# Overview.net
KiCad netlist of a schematic drawn in Altium Designer
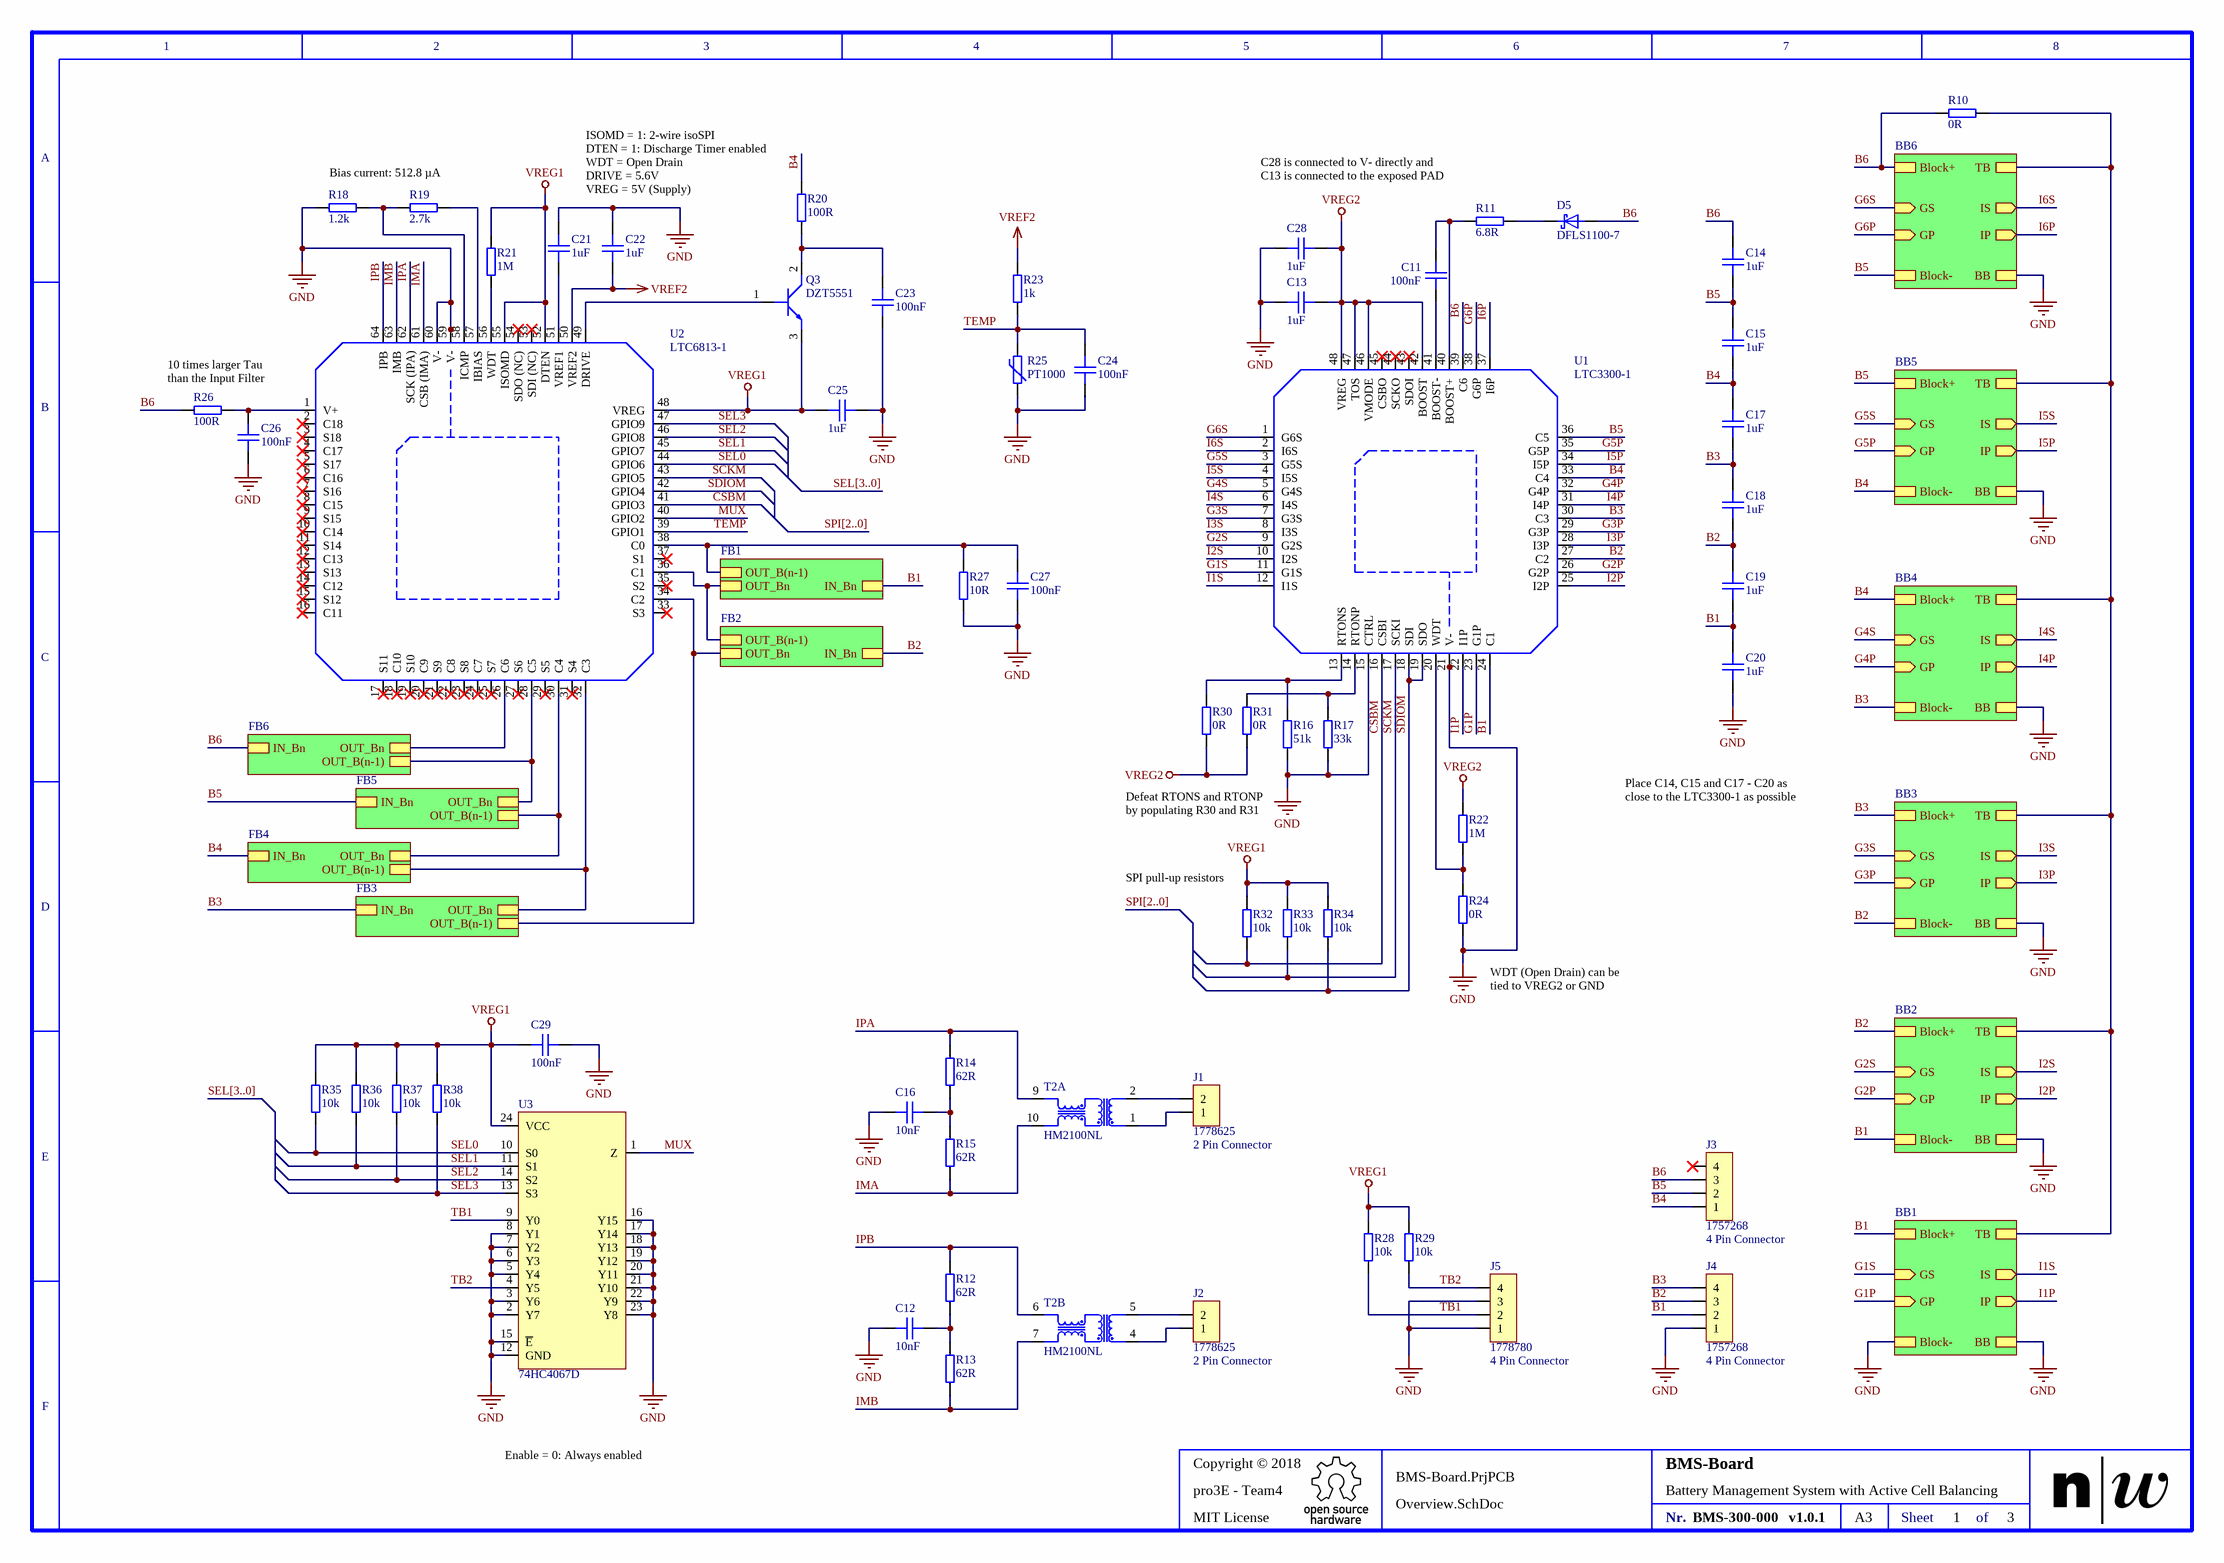
[diagram p0: Overview.SchDoc]

(export (version "E")
  (design (tool "Eeschema 10.0.6"))
  (components
    (comp (ref "C11")
      (value "100nF")
      (footprint "CAP 0603")
      (libsource (lib "SVNDatabase") (part "Capacitor"))
    )
    (comp (ref "C12")
      (value "10nF")
      (footprint "CAP 0603")
      (libsource (lib "SVNDatabase") (part "Capacitor"))
    )
    (comp (ref "C13")
      (value "1uF")
      (footprint "CAP 0603")
      (fields (field (name "TOLERANCE") "20%") (field (name "VOLTAGE") "16V"))
      (libsource (lib "SVNDatabase") (part "Capacitor"))
    )
    (comp (ref "C14")
      (value "1uF")
      (footprint "CAP 0603")
      (fields (field (name "TOLERANCE") "20%") (field (name "VOLTAGE") "16V"))
      (libsource (lib "SVNDatabase") (part "Capacitor"))
    )
    (comp (ref "C15")
      (value "1uF")
      (footprint "CAP 0603")
      (fields (field (name "TOLERANCE") "20%") (field (name "VOLTAGE") "16V"))
      (libsource (lib "SVNDatabase") (part "Capacitor"))
    )
    (comp (ref "C16")
      (value "10nF")
      (footprint "CAP 0603")
      (libsource (lib "SVNDatabase") (part "Capacitor"))
    )
    (comp (ref "C17")
      (value "1uF")
      (footprint "CAP 0603")
      (fields (field (name "TOLERANCE") "20%") (field (name "VOLTAGE") "16V"))
      (libsource (lib "SVNDatabase") (part "Capacitor"))
    )
    (comp (ref "C18")
      (value "1uF")
      (footprint "CAP 0603")
      (fields (field (name "TOLERANCE") "20%") (field (name "VOLTAGE") "16V"))
      (libsource (lib "SVNDatabase") (part "Capacitor"))
    )
    (comp (ref "C19")
      (value "1uF")
      (footprint "CAP 0603")
      (fields (field (name "TOLERANCE") "20%") (field (name "VOLTAGE") "16V"))
      (libsource (lib "SVNDatabase") (part "Capacitor"))
    )
    (comp (ref "C20")
      (value "1uF")
      (footprint "CAP 0603")
      (fields (field (name "TOLERANCE") "20%") (field (name "VOLTAGE") "16V"))
      (libsource (lib "SVNDatabase") (part "Capacitor"))
    )
    (comp (ref "C21")
      (value "1uF")
      (footprint "CAP 0603")
      (fields (field (name "TOLERANCE") "20%") (field (name "VOLTAGE") "16V"))
      (libsource (lib "SVNDatabase") (part "Capacitor"))
    )
    (comp (ref "C22")
      (value "1uF")
      (footprint "CAP 0603")
      (fields (field (name "TOLERANCE") "20%") (field (name "VOLTAGE") "16V"))
      (libsource (lib "SVNDatabase") (part "Capacitor"))
    )
    (comp (ref "C23")
      (value "100nF")
      (footprint "CAP 0603")
      (libsource (lib "SVNDatabase") (part "Capacitor"))
    )
    (comp (ref "C24")
      (value "100nF")
      (footprint "CAP 0603")
      (libsource (lib "SVNDatabase") (part "Capacitor"))
    )
    (comp (ref "C25")
      (value "1uF")
      (footprint "CAP 0603")
      (fields (field (name "TOLERANCE") "20%") (field (name "VOLTAGE") "16V"))
      (libsource (lib "SVNDatabase") (part "Capacitor"))
    )
    (comp (ref "C26")
      (value "100nF")
      (footprint "CAP 0603")
      (libsource (lib "SVNDatabase") (part "Capacitor"))
    )
    (comp (ref "C27")
      (value "100nF")
      (footprint "CAP 0603")
      (libsource (lib "SVNDatabase") (part "Capacitor"))
    )
    (comp (ref "C28")
      (value "1uF")
      (footprint "CAP 0603")
      (fields (field (name "TOLERANCE") "20%") (field (name "VOLTAGE") "16V"))
      (libsource (lib "SVNDatabase") (part "Capacitor"))
    )
    (comp (ref "C29")
      (value "100nF")
      (footprint "CAP 0603")
      (libsource (lib "SVNDatabase") (part "Capacitor"))
    )
    (comp (ref "D5")
      (value "DFLS1100-7")
      (footprint "PowerDI-123")
      (libsource (lib "SVNDatabase") (part "Schottky Diode"))
    )
    (comp (ref "J1")
      (value "1778625")
      (footprint "PTSM 0.5 2 HH THT")
      (description "2 Pin Connector")
      (fields (field (name "DESC") "2 Pin Connector"))
      (libsource (lib "SVNDatabase") (part "2 Pin"))
    )
    (comp (ref "J2")
      (value "1778625")
      (footprint "PTSM 0.5 2 HH THT")
      (description "2 Pin Connector")
      (fields (field (name "DESC") "2 Pin Connector"))
      (libsource (lib "SVNDatabase") (part "2 Pin"))
    )
    (comp (ref "J3")
      (value "1757268")
      (footprint "MSTBA 2.5 4 G THT 5.08")
      (description "4 Pin Connector")
      (fields (field (name "DESCR") "4 Pin Connector"))
      (libsource (lib "SVNDatabase") (part "4 Pin"))
    )
    (comp (ref "J4")
      (value "1757268")
      (footprint "MSTBA 2.5 4 G THT 5.08")
      (description "4 Pin Connector")
      (fields (field (name "DESCR") "4 Pin Connector"))
      (libsource (lib "SVNDatabase") (part "4 Pin"))
    )
    (comp (ref "J5")
      (value "1778780")
      (footprint "PTSM 0.5 4 HH THT")
      (description "4 Pin Connector")
      (fields (field (name "DESCR") "4 Pin Connector"))
      (libsource (lib "SVNDatabase") (part "4 Pin"))
    )
    (comp (ref "Q3") (value "DZT5551") (footprint "SOT-223") (libsource (lib "SVNDatabase") (part "BJT NPN")))
    (comp (ref "R10")
      (value "0R")
      (footprint "1206")
      (fields (field (name "TOLERANCE") "1%"))
      (libsource (lib "SVNDatabase") (part "R"))
    )
    (comp (ref "R11")
      (value "6.8R")
      (footprint "0603")
      (fields (field (name "TOLERANCE") "1%"))
      (libsource (lib "SVNDatabase") (part "R"))
    )
    (comp (ref "R12")
      (value "62R")
      (footprint "0603")
      (fields (field (name "TOLERANCE") "1%"))
      (libsource (lib "SVNDatabase") (part "R"))
    )
    (comp (ref "R13")
      (value "62R")
      (footprint "0603")
      (fields (field (name "TOLERANCE") "1%"))
      (libsource (lib "SVNDatabase") (part "R"))
    )
    (comp (ref "R14")
      (value "62R")
      (footprint "0603")
      (fields (field (name "TOLERANCE") "1%"))
      (libsource (lib "SVNDatabase") (part "R"))
    )
    (comp (ref "R15")
      (value "62R")
      (footprint "0603")
      (fields (field (name "TOLERANCE") "1%"))
      (libsource (lib "SVNDatabase") (part "R"))
    )
    (comp (ref "R16")
      (value "51k")
      (footprint "0603")
      (fields (field (name "TOLERANCE") "1%"))
      (libsource (lib "SVNDatabase") (part "R"))
    )
    (comp (ref "R17")
      (value "33k")
      (footprint "0603")
      (fields (field (name "TOLERANCE") "1%"))
      (libsource (lib "SVNDatabase") (part "R"))
    )
    (comp (ref "R18")
      (value "1.2k")
      (footprint "0603")
      (fields (field (name "TOLERANCE") "1%"))
      (libsource (lib "SVNDatabase") (part "R"))
    )
    (comp (ref "R19")
      (value "2.7k")
      (footprint "0603")
      (fields (field (name "TOLERANCE") "1%"))
      (libsource (lib "SVNDatabase") (part "R"))
    )
    (comp (ref "R20")
      (value "100R")
      (footprint "0603")
      (fields (field (name "TOLERANCE") "1%"))
      (libsource (lib "SVNDatabase") (part "R"))
    )
    (comp (ref "R21")
      (value "1M")
      (footprint "0603")
      (fields (field (name "TOLERANCE") "1%"))
      (libsource (lib "SVNDatabase") (part "R"))
    )
    (comp (ref "R22")
      (value "1M")
      (footprint "0603")
      (fields (field (name "TOLERANCE") "1%"))
      (libsource (lib "SVNDatabase") (part "R"))
    )
    (comp (ref "R23")
      (value "1k")
      (footprint "0603")
      (fields (field (name "TOLERANCE") "1%"))
      (libsource (lib "SVNDatabase") (part "R"))
    )
    (comp (ref "R24")
      (value "0R")
      (footprint "0603")
      (fields (field (name "TOLERANCE") "1%"))
      (libsource (lib "SVNDatabase") (part "R"))
    )
    (comp (ref "R25")
      (value "PT1000")
      (footprint "1206")
      (libsource (lib "SVNDatabase") (part "R Thermistor"))
    )
    (comp (ref "R26")
      (value "100R")
      (footprint "0603")
      (fields (field (name "TOLERANCE") "1%"))
      (libsource (lib "SVNDatabase") (part "R"))
    )
    (comp (ref "R27")
      (value "10R")
      (footprint "0603")
      (fields (field (name "TOLERANCE") "1%"))
      (libsource (lib "SVNDatabase") (part "R"))
    )
    (comp (ref "R28")
      (value "10k")
      (footprint "0603")
      (fields (field (name "TOLERANCE") "1%"))
      (libsource (lib "SVNDatabase") (part "R"))
    )
    (comp (ref "R29")
      (value "10k")
      (footprint "0603")
      (fields (field (name "TOLERANCE") "1%"))
      (libsource (lib "SVNDatabase") (part "R"))
    )
    (comp (ref "R30")
      (value "0R")
      (footprint "0603")
      (fields (field (name "TOLERANCE") "1%"))
      (libsource (lib "SVNDatabase") (part "R"))
    )
    (comp (ref "R31")
      (value "0R")
      (footprint "0603")
      (fields (field (name "TOLERANCE") "1%"))
      (libsource (lib "SVNDatabase") (part "R"))
    )
    (comp (ref "R32")
      (value "10k")
      (footprint "0603")
      (fields (field (name "TOLERANCE") "1%"))
      (libsource (lib "SVNDatabase") (part "R"))
    )
    (comp (ref "R33")
      (value "10k")
      (footprint "0603")
      (fields (field (name "TOLERANCE") "1%"))
      (libsource (lib "SVNDatabase") (part "R"))
    )
    (comp (ref "R34")
      (value "10k")
      (footprint "0603")
      (fields (field (name "TOLERANCE") "1%"))
      (libsource (lib "SVNDatabase") (part "R"))
    )
    (comp (ref "R35")
      (value "10k")
      (footprint "0603")
      (fields (field (name "TOLERANCE") "1%"))
      (libsource (lib "SVNDatabase") (part "R"))
    )
    (comp (ref "R36")
      (value "10k")
      (footprint "0603")
      (fields (field (name "TOLERANCE") "1%"))
      (libsource (lib "SVNDatabase") (part "R"))
    )
    (comp (ref "R37")
      (value "10k")
      (footprint "0603")
      (fields (field (name "TOLERANCE") "1%"))
      (libsource (lib "SVNDatabase") (part "R"))
    )
    (comp (ref "R38")
      (value "10k")
      (footprint "0603")
      (fields (field (name "TOLERANCE") "1%"))
      (libsource (lib "SVNDatabase") (part "R"))
    )
    (comp (ref "T2")
      (value "HM2100NL")
      (footprint "HM2100NL")
      (description "BMS Communication Transformer with Choke")
      (fields (field (name "TOLERANCE") "50%"))
      (libsource (lib "SVNDatabase") (part "HM2100NL"))
    )
    (comp (ref "U1")
      (value "LTC3300-1")
      (footprint "eLQFP-48")
      (description "Battery Balancer")
      (libsource (lib "SVNDatabase") (part "LTC3300"))
    )
    (comp (ref "U2")
      (value "LTC6813-1")
      (footprint "eLQFP-64")
      (description "Battery Monitor")
      (libsource (lib "SVNDatabase") (part "LTC6813"))
    )
    (comp (ref "U3")
      (value "74HC4067D")
      (footprint "SO-24")
      (description "MUX 16:1")
      (libsource (lib "SVNDatabase") (part "74HC4067D"))
    )
  )
  (nets
    (net (code "4") (name "/B1") (class "Default")
      (node (ref "C19") (pin "1") (pinfunction "1_1") (pintype "passive"))
      (node (ref "C20") (pin "2") (pinfunction "2_2") (pintype "passive"))
      (node (ref "J4") (pin "2") (pinfunction "2_2") (pintype "passive"))
      (node (ref "U1") (pin "24") (pinfunction "C1_24") (pintype "passive"))
    )
    (net (code "5") (name "/B2") (class "Default")
      (node (ref "C18") (pin "1") (pinfunction "1_1") (pintype "passive"))
      (node (ref "C19") (pin "2") (pinfunction "2_2") (pintype "passive"))
      (node (ref "J4") (pin "3") (pinfunction "3_3") (pintype "passive"))
      (node (ref "U1") (pin "27") (pinfunction "C2_27") (pintype "passive"))
    )
    (net (code "6") (name "/B3") (class "Default")
      (node (ref "C17") (pin "1") (pinfunction "1_1") (pintype "passive"))
      (node (ref "C18") (pin "2") (pinfunction "2_2") (pintype "passive"))
      (node (ref "J4") (pin "4") (pinfunction "4_4") (pintype "passive"))
      (node (ref "U1") (pin "30") (pinfunction "C3_30") (pintype "passive"))
    )
    (net (code "7") (name "/B4") (class "Default")
      (node (ref "C15") (pin "1") (pinfunction "1_1") (pintype "passive"))
      (node (ref "C17") (pin "2") (pinfunction "2_2") (pintype "passive"))
      (node (ref "J3") (pin "1") (pinfunction "1_1") (pintype "passive"))
      (node (ref "R20") (pin "2") (pinfunction "2_2") (pintype "passive"))
      (node (ref "U1") (pin "33") (pinfunction "C4_33") (pintype "passive"))
    )
    (net (code "8") (name "/B5") (class "Default")
      (node (ref "C14") (pin "1") (pinfunction "1_1") (pintype "passive"))
      (node (ref "C15") (pin "2") (pinfunction "2_2") (pintype "passive"))
      (node (ref "J3") (pin "2") (pinfunction "2_2") (pintype "passive"))
      (node (ref "U1") (pin "36") (pinfunction "C5_36") (pintype "passive"))
    )
    (net (code "9") (name "/B6") (class "Default")
      (node (ref "C14") (pin "2") (pinfunction "2_2") (pintype "passive"))
      (node (ref "D5") (pin "1") (pinfunction "1_1") (pintype "passive"))
      (node (ref "J3") (pin "3") (pinfunction "3_3") (pintype "passive"))
      (node (ref "R10") (pin "1") (pinfunction "1_1") (pintype "passive"))
      (node (ref "R26") (pin "1") (pinfunction "1_1") (pintype "passive"))
      (node (ref "U1") (pin "39") (pinfunction "C6_39") (pintype "passive"))
    )
    (net (code "10") (name "/CSBM") (class "Default")
      (node (ref "R32") (pin "1") (pinfunction "1_1") (pintype "passive"))
      (node (ref "U1") (pin "16") (pinfunction "CSBI_16") (pintype "passive"))
      (node (ref "U2") (pin "41") (pinfunction "GPIO3_41") (pintype "passive"))
    )
    (net (code "11") (name "/G1P") (class "Default")
      (node (ref "U1") (pin "23") (pinfunction "G1P_23") (pintype "passive"))
    )
    (net (code "12") (name "/G1S") (class "Default")
      (node (ref "U1") (pin "11") (pinfunction "G1S_11") (pintype "passive"))
    )
    (net (code "13") (name "/G2P") (class "Default")
      (node (ref "U1") (pin "26") (pinfunction "G2P_26") (pintype "passive"))
    )
    (net (code "14") (name "/G2S") (class "Default")
      (node (ref "U1") (pin "9") (pinfunction "G2S_9") (pintype "passive"))
    )
    (net (code "15") (name "/G3P") (class "Default")
      (node (ref "U1") (pin "29") (pinfunction "G3P_29") (pintype "passive"))
    )
    (net (code "16") (name "/G3S") (class "Default")
      (node (ref "U1") (pin "7") (pinfunction "G3S_7") (pintype "passive"))
    )
    (net (code "17") (name "/G4P") (class "Default")
      (node (ref "U1") (pin "32") (pinfunction "G4P_32") (pintype "passive"))
    )
    (net (code "18") (name "/G4S") (class "Default")
      (node (ref "U1") (pin "5") (pinfunction "G4S_5") (pintype "passive"))
    )
    (net (code "19") (name "/G5P") (class "Default")
      (node (ref "U1") (pin "35") (pinfunction "G5P_35") (pintype "passive"))
    )
    (net (code "20") (name "/G5S") (class "Default")
      (node (ref "U1") (pin "3") (pinfunction "G5S_3") (pintype "passive"))
    )
    (net (code "21") (name "/G6P") (class "Default")
      (node (ref "U1") (pin "38") (pinfunction "G6P_38") (pintype "passive"))
    )
    (net (code "22") (name "/G6S") (class "Default")
      (node (ref "U1") (pin "1") (pinfunction "G6S_1") (pintype "passive"))
    )
    (net (code "23") (name "/I1P") (class "Default")
      (node (ref "U1") (pin "22") (pinfunction "I1P_22") (pintype "passive"))
    )
    (net (code "24") (name "/I1S") (class "Default")
      (node (ref "U1") (pin "12") (pinfunction "I1S_12") (pintype "passive"))
    )
    (net (code "25") (name "/I2P") (class "Default")
      (node (ref "U1") (pin "25") (pinfunction "I2P_25") (pintype "passive"))
    )
    (net (code "26") (name "/I2S") (class "Default")
      (node (ref "U1") (pin "10") (pinfunction "I2S_10") (pintype "passive"))
    )
    (net (code "27") (name "/I3P") (class "Default")
      (node (ref "U1") (pin "28") (pinfunction "I3P_28") (pintype "passive"))
    )
    (net (code "28") (name "/I3S") (class "Default")
      (node (ref "U1") (pin "8") (pinfunction "I3S_8") (pintype "passive"))
    )
    (net (code "29") (name "/I4P") (class "Default")
      (node (ref "U1") (pin "31") (pinfunction "I4P_31") (pintype "passive"))
    )
    (net (code "30") (name "/I4S") (class "Default")
      (node (ref "U1") (pin "6") (pinfunction "I4S_6") (pintype "passive"))
    )
    (net (code "31") (name "/I5P") (class "Default")
      (node (ref "U1") (pin "34") (pinfunction "I5P_34") (pintype "passive"))
    )
    (net (code "32") (name "/I5S") (class "Default")
      (node (ref "U1") (pin "4") (pinfunction "I5S_4") (pintype "passive"))
    )
    (net (code "33") (name "/I6P") (class "Default")
      (node (ref "U1") (pin "37") (pinfunction "I6P_37") (pintype "passive"))
    )
    (net (code "34") (name "/I6S") (class "Default")
      (node (ref "U1") (pin "2") (pinfunction "I6S_2") (pintype "passive"))
    )
    (net (code "35") (name "/IMA") (class "Default")
      (node (ref "R15") (pin "2") (pinfunction "2_2") (pintype "passive"))
      (node (ref "T2") (pin "10") (pinfunction "10_10") (pintype "passive"))
      (node (ref "U2") (pin "61") (pinfunction "CSB_(IMA)_61") (pintype "passive"))
    )
    (net (code "36") (name "/IMB") (class "Default")
      (node (ref "R13") (pin "2") (pinfunction "2_2") (pintype "passive"))
      (node (ref "T2") (pin "7") (pinfunction "7_7") (pintype "passive"))
      (node (ref "U2") (pin "63") (pinfunction "IMB_63") (pintype "passive"))
    )
    (net (code "37") (name "/IPA") (class "Default")
      (node (ref "R14") (pin "1") (pinfunction "1_1") (pintype "passive"))
      (node (ref "T2") (pin "9") (pinfunction "9_9") (pintype "passive"))
      (node (ref "U2") (pin "62") (pinfunction "SCK_(IPA)_62") (pintype "passive"))
    )
    (net (code "38") (name "/IPB") (class "Default")
      (node (ref "R12") (pin "1") (pinfunction "1_1") (pintype "passive"))
      (node (ref "T2") (pin "6") (pinfunction "6_6") (pintype "passive"))
      (node (ref "U2") (pin "64") (pinfunction "IPB_64") (pintype "passive"))
    )
    (net (code "39") (name "/MUX") (class "Default")
      (node (ref "U2") (pin "40") (pinfunction "GPIO2_40") (pintype "passive"))
      (node (ref "U3") (pin "1") (pinfunction "Z_1") (pintype "passive"))
    )
    (net (code "40") (name "/OUT_B(n-1)") (class "Default")
      (node (ref "U2") (pin "36") (pinfunction "C1_36") (pintype "passive"))
    )
    (net (code "41") (name "/OUT_B(n-1)_1") (class "Default")
      (node (ref "U2") (pin "30") (pinfunction "C4_30") (pintype "passive"))
    )
    (net (code "42") (name "/OUT_B(n-1)_2") (class "Default")
      (node (ref "U2") (pin "32") (pinfunction "C3_32") (pintype "passive"))
    )
    (net (code "43") (name "/OUT_B(n-1)_3") (class "Default")
      (node (ref "U2") (pin "28") (pinfunction "C5_28") (pintype "passive"))
    )
    (net (code "44") (name "/OUT_B(n-1)_4") (class "Default")
      (node (ref "U2") (pin "34") (pinfunction "C2_34") (pintype "passive"))
    )
    (net (code "45") (name "/OUT_B(n-1)_5") (class "Default")
      (node (ref "C27") (pin "2") (pinfunction "2_2") (pintype "passive"))
      (node (ref "R27") (pin "2") (pinfunction "2_2") (pintype "passive"))
      (node (ref "U2") (pin "38") (pinfunction "C0_38") (pintype "passive"))
    )
    (net (code "46") (name "/OUT_Bn") (class "Default")
      (node (ref "U2") (pin "26") (pinfunction "C6_26") (pintype "passive"))
    )
    (net (code "47") (name "/SCKM") (class "Default")
      (node (ref "R33") (pin "1") (pinfunction "1_1") (pintype "passive"))
      (node (ref "U1") (pin "17") (pinfunction "SCKI_17") (pintype "passive"))
      (node (ref "U2") (pin "43") (pinfunction "GPIO5_43") (pintype "passive"))
    )
    (net (code "48") (name "/SDIOM") (class "Default")
      (node (ref "R34") (pin "1") (pinfunction "1_1") (pintype "passive"))
      (node (ref "U1") (pin "18") (pinfunction "SDI_18") (pintype "passive"))
      (node (ref "U1") (pin "19") (pinfunction "SDO_19") (pintype "passive"))
      (node (ref "U2") (pin "42") (pinfunction "GPIO4_42") (pintype "passive"))
    )
    (net (code "49") (name "/SEL0") (class "Default")
      (node (ref "R35") (pin "1") (pinfunction "1_1") (pintype "passive"))
      (node (ref "U2") (pin "44") (pinfunction "GPIO6_44") (pintype "passive"))
      (node (ref "U3") (pin "10") (pinfunction "S0_10") (pintype "passive"))
    )
    (net (code "50") (name "/SEL1") (class "Default")
      (node (ref "R36") (pin "1") (pinfunction "1_1") (pintype "passive"))
      (node (ref "U2") (pin "45") (pinfunction "GPIO7_45") (pintype "passive"))
      (node (ref "U3") (pin "11") (pinfunction "S1_11") (pintype "passive"))
    )
    (net (code "51") (name "/SEL2") (class "Default")
      (node (ref "R37") (pin "1") (pinfunction "1_1") (pintype "passive"))
      (node (ref "U2") (pin "46") (pinfunction "GPIO8_46") (pintype "passive"))
      (node (ref "U3") (pin "14") (pinfunction "S2_14") (pintype "passive"))
    )
    (net (code "52") (name "/SEL3") (class "Default")
      (node (ref "R38") (pin "1") (pinfunction "1_1") (pintype "passive"))
      (node (ref "U2") (pin "47") (pinfunction "GPIO9_47") (pintype "passive"))
      (node (ref "U3") (pin "13") (pinfunction "S3_13") (pintype "passive"))
    )
    (net (code "55") (name "/TB") (class "Default")
      (node (ref "R10") (pin "2") (pinfunction "2_2") (pintype "passive"))
    )
    (net (code "56") (name "/TB1") (class "Default")
      (node (ref "J5") (pin "2") (pinfunction "2_2") (pintype "passive"))
      (node (ref "R28") (pin "1") (pinfunction "1_1") (pintype "passive"))
      (node (ref "U3") (pin "9") (pinfunction "Y0_9") (pintype "passive"))
    )
    (net (code "57") (name "/TB2") (class "Default")
      (node (ref "J5") (pin "4") (pinfunction "4_4") (pintype "passive"))
      (node (ref "R29") (pin "1") (pinfunction "1_1") (pintype "passive"))
      (node (ref "U3") (pin "4") (pinfunction "Y5_4") (pintype "passive"))
    )
    (net (code "58") (name "/TEMP") (class "Default")
      (node (ref "C24") (pin "2") (pinfunction "2_2") (pintype "passive"))
      (node (ref "R23") (pin "1") (pinfunction "1_1") (pintype "passive"))
      (node (ref "R25") (pin "1") (pinfunction "1_1") (pintype "passive"))
      (node (ref "U2") (pin "39") (pinfunction "GPIO1_39") (pintype "passive"))
    )
    (net (code "59") (name "GND") (class "Default")
      (node (ref "C12") (pin "1") (pinfunction "1_1") (pintype "passive"))
      (node (ref "C13") (pin "2") (pinfunction "2_2") (pintype "passive"))
      (node (ref "C16") (pin "1") (pinfunction "1_1") (pintype "passive"))
      (node (ref "C20") (pin "1") (pinfunction "1_1") (pintype "passive"))
      (node (ref "C21") (pin "2") (pinfunction "2_2") (pintype "passive"))
      (node (ref "C22") (pin "1") (pinfunction "1_1") (pintype "passive"))
      (node (ref "C23") (pin "1") (pinfunction "1_1") (pintype "passive"))
      (node (ref "C24") (pin "1") (pinfunction "1_1") (pintype "passive"))
      (node (ref "C25") (pin "1") (pinfunction "1_1") (pintype "passive"))
      (node (ref "C26") (pin "1") (pinfunction "1_1") (pintype "passive"))
      (node (ref "C27") (pin "1") (pinfunction "1_1") (pintype "passive"))
      (node (ref "C28") (pin "1") (pinfunction "1_1") (pintype "passive"))
      (node (ref "C29") (pin "1") (pinfunction "1_1") (pintype "passive"))
      (node (ref "J4") (pin "1") (pinfunction "1_1") (pintype "passive"))
      (node (ref "J5") (pin "1") (pinfunction "1_1") (pintype "passive"))
      (node (ref "J5") (pin "3") (pinfunction "3_3") (pintype "passive"))
      (node (ref "R16") (pin "1") (pinfunction "1_1") (pintype "passive"))
      (node (ref "R17") (pin "1") (pinfunction "1_1") (pintype "passive"))
      (node (ref "R18") (pin "2") (pinfunction "2_2") (pintype "passive"))
      (node (ref "R24") (pin "1") (pinfunction "1_1") (pintype "passive"))
      (node (ref "R25") (pin "2") (pinfunction "2_2") (pintype "passive"))
      (node (ref "R27") (pin "1") (pinfunction "1_1") (pintype "passive"))
      (node (ref "U1") (pin "15") (pinfunction "CTRL_15") (pintype "passive"))
      (node (ref "U1") (pin "21") (pinfunction "V-_21") (pintype "passive"))
      (node (ref "U1") (pin "49") (pinfunction "V-_49") (pintype "passive"))
      (node (ref "U2") (pin "59") (pinfunction "V-_59") (pintype "passive"))
      (node (ref "U2") (pin "60") (pinfunction "V-_60") (pintype "passive"))
      (node (ref "U2") (pin "65") (pinfunction "V-_65") (pintype "passive"))
      (node (ref "U3") (pin "12") (pinfunction "GND_12") (pintype "passive"))
      (node (ref "U3") (pin "15") (pinfunction "~{E}_15") (pintype "passive"))
      (node (ref "U3") (pin "16") (pinfunction "Y15_16") (pintype "passive"))
      (node (ref "U3") (pin "17") (pinfunction "Y14_17") (pintype "passive"))
      (node (ref "U3") (pin "18") (pinfunction "Y13_18") (pintype "passive"))
      (node (ref "U3") (pin "19") (pinfunction "Y12_19") (pintype "passive"))
      (node (ref "U3") (pin "2") (pinfunction "Y7_2") (pintype "passive"))
      (node (ref "U3") (pin "20") (pinfunction "Y11_20") (pintype "passive"))
      (node (ref "U3") (pin "21") (pinfunction "Y10_21") (pintype "passive"))
      (node (ref "U3") (pin "22") (pinfunction "Y9_22") (pintype "passive"))
      (node (ref "U3") (pin "23") (pinfunction "Y8_23") (pintype "passive"))
      (node (ref "U3") (pin "3") (pinfunction "Y6_3") (pintype "passive"))
      (node (ref "U3") (pin "5") (pinfunction "Y4_5") (pintype "passive"))
      (node (ref "U3") (pin "6") (pinfunction "Y3_6") (pintype "passive"))
      (node (ref "U3") (pin "7") (pinfunction "Y2_7") (pintype "passive"))
      (node (ref "U3") (pin "8") (pinfunction "Y1_8") (pintype "passive"))
    )
    (net (code "60") (name "Net-(C12-Pad2)") (class "Default")
      (node (ref "C12") (pin "2") (pinfunction "2_2") (pintype "passive"))
      (node (ref "R12") (pin "2") (pinfunction "2_2") (pintype "passive"))
      (node (ref "R13") (pin "1") (pinfunction "1_1") (pintype "passive"))
    )
    (net (code "61") (name "Net-(C16-Pad2)") (class "Default")
      (node (ref "C16") (pin "2") (pinfunction "2_2") (pintype "passive"))
      (node (ref "R14") (pin "2") (pinfunction "2_2") (pintype "passive"))
      (node (ref "R15") (pin "1") (pinfunction "1_1") (pintype "passive"))
    )
    (net (code "62") (name "Net-(D5-Pad2)") (class "Default")
      (node (ref "D5") (pin "2") (pinfunction "2_2") (pintype "passive"))
      (node (ref "R11") (pin "2") (pinfunction "2_2") (pintype "passive"))
    )
    (net (code "63") (name "Net-(J1-Pad1)") (class "Default")
      (node (ref "J1") (pin "1") (pinfunction "1_1") (pintype "passive"))
      (node (ref "T2") (pin "1") (pinfunction "1_1") (pintype "passive"))
    )
    (net (code "64") (name "Net-(J1-Pad2)") (class "Default")
      (node (ref "J1") (pin "2") (pinfunction "2_2") (pintype "passive"))
      (node (ref "T2") (pin "2") (pinfunction "2_2") (pintype "passive"))
    )
    (net (code "65") (name "Net-(J2-Pad1)") (class "Default")
      (node (ref "J2") (pin "1") (pinfunction "1_1") (pintype "passive"))
      (node (ref "T2") (pin "4") (pinfunction "4_4") (pintype "passive"))
    )
    (net (code "66") (name "Net-(J2-Pad2)") (class "Default")
      (node (ref "J2") (pin "2") (pinfunction "2_2") (pintype "passive"))
      (node (ref "T2") (pin "5") (pinfunction "5_5") (pintype "passive"))
    )
    (net (code "67") (name "Net-(Q3-D)") (class "Default")
      (node (ref "C23") (pin "2") (pinfunction "2_2") (pintype "passive"))
      (node (ref "Q3") (pin "2") (pinfunction "D_2") (pintype "passive"))
      (node (ref "R20") (pin "1") (pinfunction "1_1") (pintype "passive"))
    )
    (net (code "68") (name "Net-(Q3-G)") (class "Default")
      (node (ref "Q3") (pin "1") (pinfunction "G_1") (pintype "passive"))
      (node (ref "U2") (pin "49") (pinfunction "DRIVE_49") (pintype "passive"))
    )
    (net (code "69") (name "Net-(U1-BOOST+)") (class "Default")
      (node (ref "C11") (pin "2") (pinfunction "2_2") (pintype "passive"))
      (node (ref "R11") (pin "1") (pinfunction "1_1") (pintype "passive"))
      (node (ref "U1") (pin "40") (pinfunction "BOOST+_40") (pintype "passive"))
    )
    (net (code "70") (name "Net-(U1-BOOST-)") (class "Default")
      (node (ref "C11") (pin "1") (pinfunction "1_1") (pintype "passive"))
      (node (ref "U1") (pin "41") (pinfunction "BOOST-_41") (pintype "passive"))
    )
    (net (code "71") (name "Net-(U1-RTONP)") (class "Default")
      (node (ref "R17") (pin "2") (pinfunction "2_2") (pintype "passive"))
      (node (ref "R31") (pin "2") (pinfunction "2_2") (pintype "passive"))
      (node (ref "U1") (pin "14") (pinfunction "RTONP_14") (pintype "passive"))
    )
    (net (code "72") (name "Net-(U1-RTONS)") (class "Default")
      (node (ref "R16") (pin "2") (pinfunction "2_2") (pintype "passive"))
      (node (ref "R30") (pin "2") (pinfunction "2_2") (pintype "passive"))
      (node (ref "U1") (pin "13") (pinfunction "RTONS_13") (pintype "passive"))
    )
    (net (code "73") (name "Net-(U1-WDT)") (class "Default")
      (node (ref "R22") (pin "1") (pinfunction "1_1") (pintype "passive"))
      (node (ref "R24") (pin "2") (pinfunction "2_2") (pintype "passive"))
      (node (ref "U1") (pin "20") (pinfunction "WDT_20") (pintype "passive"))
    )
    (net (code "74") (name "Net-(U2-IBIAS)") (class "Default")
      (node (ref "R19") (pin "1") (pinfunction "1_1") (pintype "passive"))
      (node (ref "U2") (pin "57") (pinfunction "IBIAS_57") (pintype "passive"))
    )
    (net (code "75") (name "Net-(U2-ICMP)") (class "Default")
      (node (ref "R18") (pin "1") (pinfunction "1_1") (pintype "passive"))
      (node (ref "R19") (pin "2") (pinfunction "2_2") (pintype "passive"))
      (node (ref "U2") (pin "58") (pinfunction "ICMP_58") (pintype "passive"))
    )
    (net (code "76") (name "Net-(U2-V+)") (class "Default")
      (node (ref "C26") (pin "2") (pinfunction "2_2") (pintype "passive"))
      (node (ref "R26") (pin "2") (pinfunction "2_2") (pintype "passive"))
      (node (ref "U2") (pin "1") (pinfunction "V+_1") (pintype "passive"))
    )
    (net (code "77") (name "Net-(U2-VREF1)") (class "Default")
      (node (ref "C21") (pin "1") (pinfunction "1_1") (pintype "passive"))
      (node (ref "U2") (pin "51") (pinfunction "VREF1_51") (pintype "passive"))
    )
    (net (code "78") (name "Net-(U2-WDT)") (class "Default")
      (node (ref "R21") (pin "1") (pinfunction "1_1") (pintype "passive"))
      (node (ref "U2") (pin "56") (pinfunction "WDT_56") (pintype "passive"))
    )
    (net (code "79") (name "VREF2") (class "Default")
      (node (ref "C22") (pin "2") (pinfunction "2_2") (pintype "passive"))
      (node (ref "R23") (pin "2") (pinfunction "2_2") (pintype "passive"))
      (node (ref "U2") (pin "50") (pinfunction "VREF2_50") (pintype "passive"))
    )
    (net (code "80") (name "VREG1") (class "Default")
      (node (ref "C25") (pin "2") (pinfunction "2_2") (pintype "passive"))
      (node (ref "C29") (pin "2") (pinfunction "2_2") (pintype "passive"))
      (node (ref "Q3") (pin "3") (pinfunction "S_3") (pintype "passive"))
      (node (ref "R21") (pin "2") (pinfunction "2_2") (pintype "passive"))
      (node (ref "R28") (pin "2") (pinfunction "2_2") (pintype "passive"))
      (node (ref "R29") (pin "2") (pinfunction "2_2") (pintype "passive"))
      (node (ref "R32") (pin "2") (pinfunction "2_2") (pintype "passive"))
      (node (ref "R33") (pin "2") (pinfunction "2_2") (pintype "passive"))
      (node (ref "R34") (pin "2") (pinfunction "2_2") (pintype "passive"))
      (node (ref "R35") (pin "2") (pinfunction "2_2") (pintype "passive"))
      (node (ref "R36") (pin "2") (pinfunction "2_2") (pintype "passive"))
      (node (ref "R37") (pin "2") (pinfunction "2_2") (pintype "passive"))
      (node (ref "R38") (pin "2") (pinfunction "2_2") (pintype "passive"))
      (node (ref "U2") (pin "48") (pinfunction "VREG_48") (pintype "passive"))
      (node (ref "U2") (pin "52") (pinfunction "DTEN_52") (pintype "passive"))
      (node (ref "U2") (pin "55") (pinfunction "ISOMD_55") (pintype "passive"))
      (node (ref "U3") (pin "24") (pinfunction "VCC_24") (pintype "passive"))
    )
    (net (code "81") (name "VREG2") (class "Default")
      (node (ref "C13") (pin "1") (pinfunction "1_1") (pintype "passive"))
      (node (ref "C28") (pin "2") (pinfunction "2_2") (pintype "passive"))
      (node (ref "R22") (pin "2") (pinfunction "2_2") (pintype "passive"))
      (node (ref "R30") (pin "1") (pinfunction "1_1") (pintype "passive"))
      (node (ref "R31") (pin "1") (pinfunction "1_1") (pintype "passive"))
      (node (ref "U1") (pin "42") (pinfunction "BOOST_42") (pintype "passive"))
      (node (ref "U1") (pin "46") (pinfunction "VMODE_46") (pintype "passive"))
      (node (ref "U1") (pin "47") (pinfunction "TOS_47") (pintype "passive"))
      (node (ref "U1") (pin "48") (pinfunction "VREG_48") (pintype "passive"))
    )
    (net (code "82") (name "unconnected-(J3-Pad4)") (class "Default")
      (node (ref "J3") (pin "4") (pinfunction "4_4") (pintype "passive+no_connect"))
    )
    (net (code "83") (name "unconnected-(U1-CSBO-Pad45)") (class "Default")
      (node (ref "U1") (pin "45") (pinfunction "CSBO_45") (pintype "passive+no_connect"))
    )
    (net (code "84") (name "unconnected-(U1-SCKO-Pad44)") (class "Default")
      (node (ref "U1") (pin "44") (pinfunction "SCKO_44") (pintype "passive+no_connect"))
    )
    (net (code "85") (name "unconnected-(U1-SDOI-Pad43)") (class "Default")
      (node (ref "U1") (pin "43") (pinfunction "SDOI_43") (pintype "passive+no_connect"))
    )
    (net (code "86") (name "unconnected-(U2-C7-Pad24)") (class "Default")
      (node (ref "U2") (pin "24") (pinfunction "C7_24") (pintype "passive+no_connect"))
    )
    (net (code "87") (name "unconnected-(U2-C8-Pad22)") (class "Default")
      (node (ref "U2") (pin "22") (pinfunction "C8_22") (pintype "passive+no_connect"))
    )
    (net (code "88") (name "unconnected-(U2-C9-Pad20)") (class "Default")
      (node (ref "U2") (pin "20") (pinfunction "C9_20") (pintype "passive+no_connect"))
    )
    (net (code "89") (name "unconnected-(U2-C10-Pad18)") (class "Default")
      (node (ref "U2") (pin "18") (pinfunction "C10_18") (pintype "passive+no_connect"))
    )
    (net (code "90") (name "unconnected-(U2-C11-Pad16)") (class "Default")
      (node (ref "U2") (pin "16") (pinfunction "C11_16") (pintype "passive+no_connect"))
    )
    (net (code "91") (name "unconnected-(U2-C12-Pad14)") (class "Default")
      (node (ref "U2") (pin "14") (pinfunction "C12_14") (pintype "passive+no_connect"))
    )
    (net (code "92") (name "unconnected-(U2-C13-Pad12)") (class "Default")
      (node (ref "U2") (pin "12") (pinfunction "C13_12") (pintype "passive+no_connect"))
    )
    (net (code "93") (name "unconnected-(U2-C14-Pad10)") (class "Default")
      (node (ref "U2") (pin "10") (pinfunction "C14_10") (pintype "passive+no_connect"))
    )
    (net (code "94") (name "unconnected-(U2-C15-Pad8)") (class "Default")
      (node (ref "U2") (pin "8") (pinfunction "C15_8") (pintype "passive+no_connect"))
    )
    (net (code "95") (name "unconnected-(U2-C16-Pad6)") (class "Default")
      (node (ref "U2") (pin "6") (pinfunction "C16_6") (pintype "passive+no_connect"))
    )
    (net (code "96") (name "unconnected-(U2-C17-Pad4)") (class "Default")
      (node (ref "U2") (pin "4") (pinfunction "C17_4") (pintype "passive+no_connect"))
    )
    (net (code "97") (name "unconnected-(U2-C18-Pad2)") (class "Default")
      (node (ref "U2") (pin "2") (pinfunction "C18_2") (pintype "passive+no_connect"))
    )
    (net (code "98") (name "unconnected-(U2-S1-Pad37)") (class "Default")
      (node (ref "U2") (pin "37") (pinfunction "S1_37") (pintype "passive+no_connect"))
    )
    (net (code "99") (name "unconnected-(U2-S2-Pad35)") (class "Default")
      (node (ref "U2") (pin "35") (pinfunction "S2_35") (pintype "passive+no_connect"))
    )
    (net (code "100") (name "unconnected-(U2-S3-Pad33)") (class "Default")
      (node (ref "U2") (pin "33") (pinfunction "S3_33") (pintype "passive+no_connect"))
    )
    (net (code "101") (name "unconnected-(U2-S4-Pad31)") (class "Default")
      (node (ref "U2") (pin "31") (pinfunction "S4_31") (pintype "passive+no_connect"))
    )
    (net (code "102") (name "unconnected-(U2-S5-Pad29)") (class "Default")
      (node (ref "U2") (pin "29") (pinfunction "S5_29") (pintype "passive+no_connect"))
    )
    (net (code "103") (name "unconnected-(U2-S6-Pad27)") (class "Default")
      (node (ref "U2") (pin "27") (pinfunction "S6_27") (pintype "passive+no_connect"))
    )
    (net (code "104") (name "unconnected-(U2-S7-Pad25)") (class "Default")
      (node (ref "U2") (pin "25") (pinfunction "S7_25") (pintype "passive+no_connect"))
    )
    (net (code "105") (name "unconnected-(U2-S8-Pad23)") (class "Default")
      (node (ref "U2") (pin "23") (pinfunction "S8_23") (pintype "passive+no_connect"))
    )
    (net (code "106") (name "unconnected-(U2-S9-Pad21)") (class "Default")
      (node (ref "U2") (pin "21") (pinfunction "S9_21") (pintype "passive+no_connect"))
    )
    (net (code "107") (name "unconnected-(U2-S10-Pad19)") (class "Default")
      (node (ref "U2") (pin "19") (pinfunction "S10_19") (pintype "passive+no_connect"))
    )
    (net (code "108") (name "unconnected-(U2-S11-Pad17)") (class "Default")
      (node (ref "U2") (pin "17") (pinfunction "S11_17") (pintype "passive+no_connect"))
    )
    (net (code "109") (name "unconnected-(U2-S12-Pad15)") (class "Default")
      (node (ref "U2") (pin "15") (pinfunction "S12_15") (pintype "passive+no_connect"))
    )
    (net (code "110") (name "unconnected-(U2-S13-Pad13)") (class "Default")
      (node (ref "U2") (pin "13") (pinfunction "S13_13") (pintype "passive+no_connect"))
    )
    (net (code "111") (name "unconnected-(U2-S14-Pad11)") (class "Default")
      (node (ref "U2") (pin "11") (pinfunction "S14_11") (pintype "passive+no_connect"))
    )
    (net (code "112") (name "unconnected-(U2-S15-Pad9)") (class "Default")
      (node (ref "U2") (pin "9") (pinfunction "S15_9") (pintype "passive+no_connect"))
    )
    (net (code "113") (name "unconnected-(U2-S16-Pad7)") (class "Default")
      (node (ref "U2") (pin "7") (pinfunction "S16_7") (pintype "passive+no_connect"))
    )
    (net (code "114") (name "unconnected-(U2-S17-Pad5)") (class "Default")
      (node (ref "U2") (pin "5") (pinfunction "S17_5") (pintype "passive+no_connect"))
    )
    (net (code "115") (name "unconnected-(U2-S18-Pad3)") (class "Default")
      (node (ref "U2") (pin "3") (pinfunction "S18_3") (pintype "passive+no_connect"))
    )
    (net (code "116") (name "unconnected-(U2-SDI_(NC)-Pad53)") (class "Default")
      (node (ref "U2") (pin "53") (pinfunction "SDI_(NC)_53") (pintype "passive+no_connect"))
    )
    (net (code "117") (name "unconnected-(U2-SDO_(NC)-Pad54)") (class "Default")
      (node (ref "U2") (pin "54") (pinfunction "SDO_(NC)_54") (pintype "passive+no_connect"))
    )
  )
)
